# CH32V205CCT-R0.net
KiCad netlist of a schematic drawn in Altium Designer
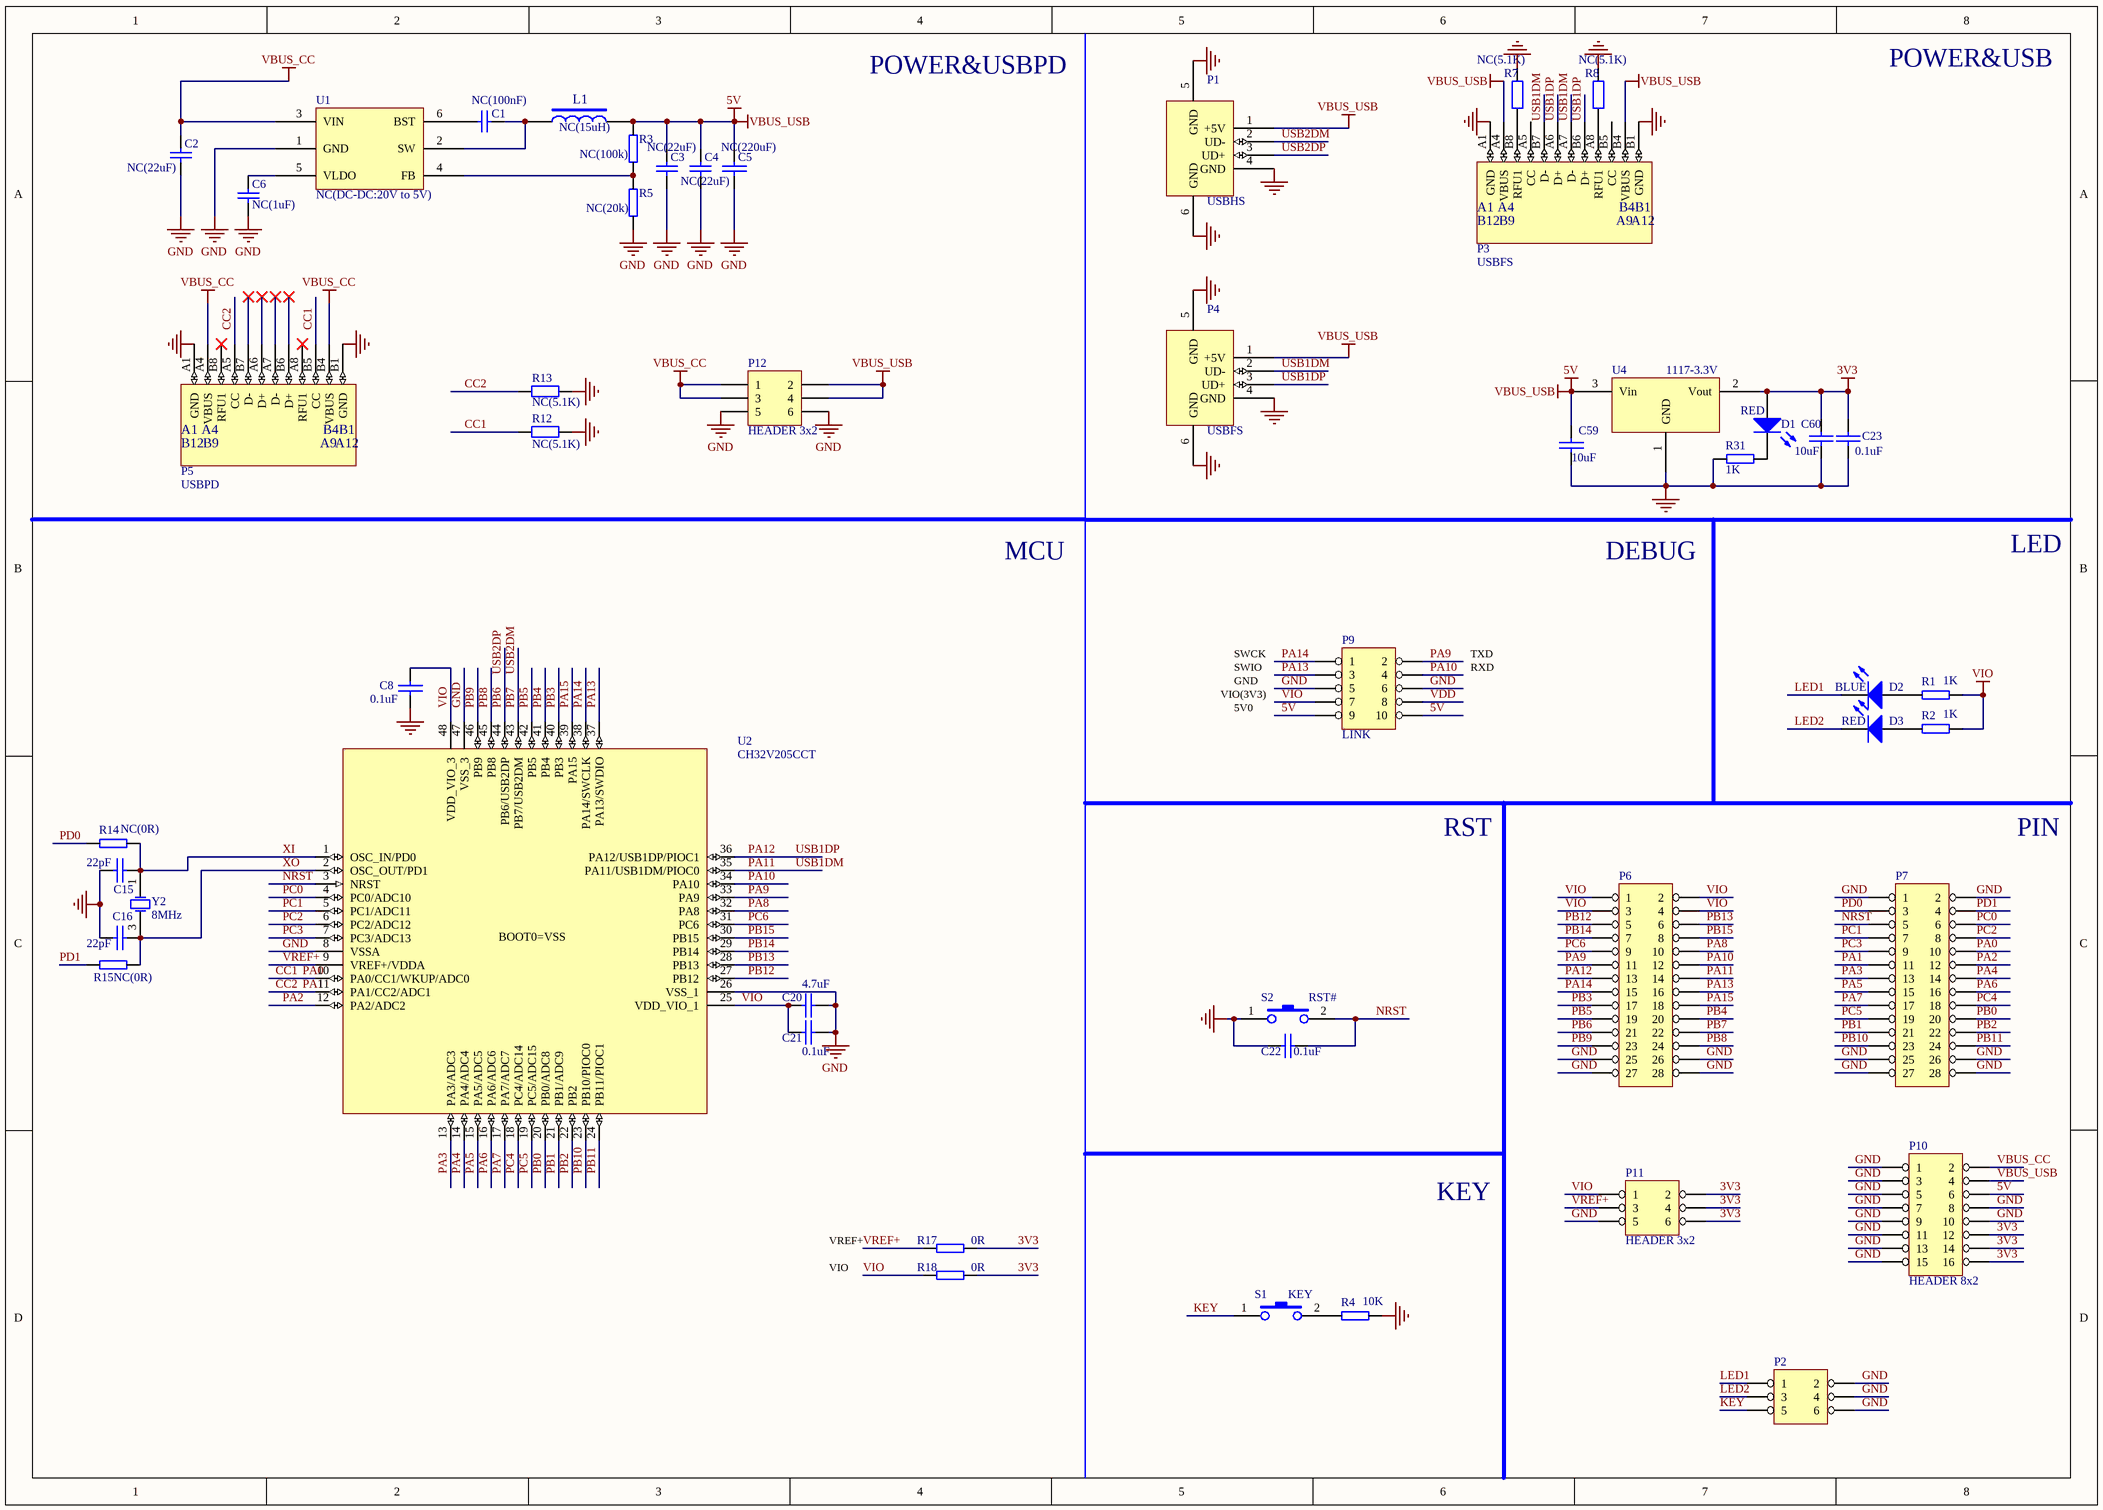
[diagram p0: CH32V205CCT-R0.SchDoc]

(export (version "E")
  (design (tool "Eeschema 10.0.6"))
  (components
    (comp (ref "C1")
      (value "NC(100nF)")
      (footprint "0402_C")
      (description "贴片电容")
      (libsource (lib "Miscellaneous Devices LC") (part "0603 100nF (104) 10% 50V"))
    )
    (comp (ref "C2")
      (value "NC(22uF)")
      (footprint "0805_C")
      (description "贴片电容")
      (libsource (lib "Miscellaneous Devices LC") (part "0603 100nF (104) 10% 50V"))
    )
    (comp (ref "C3")
      (value "NC(22uF)")
      (footprint "0805_C")
      (description "贴片电容")
      (libsource (lib "Miscellaneous Devices LC") (part "0603 100nF (104) 10% 50V"))
    )
    (comp (ref "C4")
      (value "NC(22uF)")
      (footprint "0805_C")
      (description "贴片电容")
      (libsource (lib "Miscellaneous Devices LC") (part "0603 100nF (104) 10% 50V"))
    )
    (comp (ref "C5")
      (value "NC(220uF)")
      (footprint "CD0.1")
      (description "Capacitor")
      (libsource (lib "") (part "CAP_1"))
    )
    (comp (ref "C6")
      (value "NC(1uF)")
      (footprint "0402_C")
      (description "贴片电容")
      (libsource (lib "Miscellaneous Devices LC") (part "0603 100nF (104) 10% 50V"))
    )
    (comp (ref "C8")
      (value "0.1uF")
      (footprint "0603_C")
      (description "Capacitor")
      (libsource (lib "*") (part "CAP"))
    )
    (comp (ref "C15")
      (value "22pF")
      (footprint "0603_C")
      (description "Capacitor")
      (libsource (lib "*") (part "CAP"))
    )
    (comp (ref "C16")
      (value "22pF")
      (footprint "0603_C")
      (description "Capacitor")
      (libsource (lib "*") (part "CAP"))
    )
    (comp (ref "C20")
      (value "4.7uF")
      (footprint "0603_C")
      (description "Capacitor")
      (libsource (lib "*") (part "CAP"))
    )
    (comp (ref "C21")
      (value "0.1uF")
      (footprint "0603_C")
      (description "Capacitor")
      (libsource (lib "*") (part "CAP"))
    )
    (comp (ref "C22")
      (value "0.1uF")
      (footprint "0603_C")
      (description "Capacitor")
      (libsource (lib "") (part "CAP_2"))
    )
    (comp (ref "C23")
      (value "0.1uF")
      (footprint "0402_C")
      (description "Capacitor")
      (libsource (lib "*") (part "CAP"))
    )
    (comp (ref "C59")
      (value "10uF")
      (footprint "0603_C")
      (description "Capacitor")
      (libsource (lib "*") (part "CAP"))
    )
    (comp (ref "C60")
      (value "10uF")
      (footprint "0603_C")
      (description "Capacitor")
      (libsource (lib "*") (part "CAP"))
    )
    (comp (ref "D1")
      (value "RED")
      (footprint "0603+")
      (description "Typical INFRARED GaAs LED")
      (fields (field (name "PUBLISHER") "Altium Limited"))
      (libsource (lib "*") (part "LED0"))
    )
    (comp (ref "D2")
      (value "BLUE")
      (footprint "0603+")
      (description "Typical INFRARED GaAs LED")
      (fields (field (name "PUBLISHER") "Altium Limited"))
      (libsource (lib "*") (part "LED0"))
    )
    (comp (ref "D3")
      (value "RED")
      (footprint "0603+")
      (description "Typical INFRARED GaAs LED")
      (fields (field (name "PUBLISHER") "Altium Limited"))
      (libsource (lib "*") (part "LED0"))
    )
    (comp (ref "L1")
      (value "NC(15uH)")
      (footprint "SMD_6x6mm")
      (libsource (lib "wch_sch_others") (part "INDUCTOR"))
    )
    (comp (ref "P1")
      (value "USBHS")
      (footprint "USBAF")
      (description "USB Port")
      (libsource (lib "*") (part "USB"))
    )
    (comp (ref "P2")
      (value "IO")
      (footprint "MYPCB:IDC6-2.54mm")
      (description "Header, 3-Pin, Dual row")
      (libsource (lib "wch_sch_others") (part "HEADER 3x2"))
    )
    (comp (ref "P3")
      (value "USBFS")
      (footprint "TYPE-C-Receptacle-2.0")
      (libsource (lib "*") (part "TYPE-C1"))
    )
    (comp (ref "P4")
      (value "USBFS")
      (footprint "USBAF")
      (description "USB Port")
      (libsource (lib "*") (part "USB"))
    )
    (comp (ref "P5")
      (value "USBPD")
      (footprint "TYPE-C-Receptacle-2.0")
      (libsource (lib "*") (part "TYPE-C1"))
    )
    (comp (ref "P6")
      (value "~")
      (footprint "MYPCB:IDC28-2.54MM")
      (description "Header, 14-Pin, Dual row")
      (libsource (lib "wch_sch_others") (part "HEADER 14x2"))
    )
    (comp (ref "P7")
      (value "~")
      (footprint "MYPCB:IDC28-2.54MM")
      (description "Header, 14-Pin, Dual row")
      (libsource (lib "wch_sch_others") (part "HEADER 14x2"))
    )
    (comp (ref "P9")
      (value "LINK")
      (footprint "MYPCB:IDC10-2.54mm")
      (description "Header, 5-Pin, Dual row")
      (libsource (lib "wch_sch_others") (part "HEADER 5x2"))
    )
    (comp (ref "P10")
      (value "HEADER 8x2")
      (footprint "MYPCB:IDC16-2.54mm")
      (description "Header, 8-Pin, Dual row")
      (libsource (lib "wch_sch_others") (part "HEADER 8x2"))
    )
    (comp (ref "P11")
      (value "HEADER 3x2")
      (footprint "MYPCB:IDC6-2.54mm")
      (description "Header, 3-Pin, Dual row")
      (libsource (lib "wch_sch_others") (part "HEADER 3x2"))
    )
    (comp (ref "P12")
      (value "HEADER 3x2")
      (footprint "MYPCB:IDC6-2.54mm")
      (description "Header, 3-Pin, Dual row")
      (libsource (lib "") (part "HEADER 3x2_1"))
    )
    (comp (ref "R1") (value "1K") (footprint "CHXXX:0603") (libsource (lib "wch_sch_others") (part "RES")))
    (comp (ref "R2") (value "1K") (footprint "CHXXX:0603") (libsource (lib "wch_sch_others") (part "RES")))
    (comp (ref "R3") (value "NC(100k)") (footprint "CHXXX:0603") (libsource (lib "") (part "RES_1")))
    (comp (ref "R4") (value "10K") (footprint "CHXXX:0603") (libsource (lib "wch_sch_others") (part "RES")))
    (comp (ref "R5") (value "NC(20k)") (footprint "CHXXX:0603") (libsource (lib "") (part "RES_1")))
    (comp (ref "R7")
      (value "NC(5.1K)")
      (footprint "0402")
      (description "Resistor")
      (libsource (lib "") (part "Res2_1"))
    )
    (comp (ref "R8")
      (value "NC(5.1K)")
      (footprint "0402")
      (description "Resistor")
      (libsource (lib "") (part "Res2_1"))
    )
    (comp (ref "R12")
      (value "NC(5.1K)")
      (footprint "0402")
      (description "Resistor")
      (libsource (lib "Miscellaneous Devices") (part "Res2"))
    )
    (comp (ref "R13")
      (value "NC(5.1K)")
      (footprint "0402")
      (description "Resistor")
      (libsource (lib "Miscellaneous Devices") (part "Res2"))
    )
    (comp (ref "R14")
      (value "NC(0R)")
      (footprint "CHXXX:0603")
      (libsource (lib "wch_sch_others") (part "RES"))
    )
    (comp (ref "R15")
      (value "NC(0R)")
      (footprint "CHXXX:0603")
      (libsource (lib "wch_sch_others") (part "RES"))
    )
    (comp (ref "R17") (value "0R") (footprint "CHXXX:0603") (libsource (lib "*") (part "R")))
    (comp (ref "R18") (value "0R") (footprint "CHXXX:0603") (libsource (lib "*") (part "R")))
    (comp (ref "R31") (value "1K") (footprint "0402") (libsource (lib "wch_sch_others") (part "RES")))
    (comp (ref "S1")
      (value "KEY")
      (footprint "SMD_6.1x3.65x2.5mm-KEY")
      (libsource (lib "wch_sch_others") (part "KEY1"))
    )
    (comp (ref "S2")
      (value "RST#")
      (footprint "SMD_6.1x3.65x2.5mm-KEY")
      (libsource (lib "wch_sch_others") (part "KEY1"))
    )
    (comp (ref "U1")
      (value "NC(DC-DC:20V to 5V)")
      (description "DCDC")
      (libsource (lib "wch_sch_others") (part "TPS54202"))
    )
    (comp (ref "U2")
      (value "CH32V205CCT")
      (footprint "LQFP48")
      (description "RISC-V MCU, 192MHz, USB_480M, USB FS, PD, PIOC, ADC, TKEY, 2*OPA, 2*CMP")
      (libsource (lib "CHXXX") (part "CH32V205CCT"))
    )
    (comp (ref "U4")
      (value "1117-3.3V")
      (footprint "SOT-223")
      (libsource (lib "wch_sch_others") (part "1117-3.3V"))
    )
    (comp (ref "Y2")
      (value "8MHz")
      (footprint "XT3225")
      (description "Crystal Oscillator")
      (fields (field (name "PUBLISHER") "Altium Limited"))
      (libsource (lib "*") (part "XTAL"))
    )
  )
  (nets
    (net (code "2") (name "/CC1") (class "Default")
      (node (ref "P5") (pin "B5") (pinfunction "CC_B5") (pintype "bidirectional"))
      (node (ref "P7") (pin "10") (pinfunction "10_10") (pintype "passive"))
      (node (ref "R12") (pin "1") (pinfunction "1_1") (pintype "passive"))
      (node (ref "U2") (pin "10") (pinfunction "PA0/CC1/WKUP/ADC0_10") (pintype "bidirectional"))
    )
    (net (code "3") (name "/CC2") (class "Default")
      (node (ref "P5") (pin "A5") (pinfunction "CC_A5") (pintype "bidirectional"))
      (node (ref "P7") (pin "11") (pinfunction "11_11") (pintype "passive"))
      (node (ref "R13") (pin "1") (pinfunction "1_1") (pintype "passive"))
      (node (ref "U2") (pin "11") (pinfunction "PA1/CC2/ADC1_11") (pintype "bidirectional"))
    )
    (net (code "4") (name "/KEY") (class "Default")
      (node (ref "P2") (pin "5") (pinfunction "5_5") (pintype "passive"))
      (node (ref "S1") (pin "1") (pinfunction "1_1") (pintype "passive"))
    )
    (net (code "5") (name "/LED1") (class "Default")
      (node (ref "D2") (pin "2") (pinfunction "K_2") (pintype "passive"))
      (node (ref "P2") (pin "1") (pinfunction "1_1") (pintype "passive"))
    )
    (net (code "6") (name "/LED2") (class "Default")
      (node (ref "D3") (pin "2") (pinfunction "K_2") (pintype "passive"))
      (node (ref "P2") (pin "3") (pinfunction "3_3") (pintype "passive"))
    )
    (net (code "7") (name "/NRST") (class "Default")
      (node (ref "C22") (pin "2") (pinfunction "2_2") (pintype "passive"))
      (node (ref "P7") (pin "5") (pinfunction "5_5") (pintype "passive"))
      (node (ref "S2") (pin "2") (pinfunction "2_2") (pintype "passive"))
      (node (ref "U2") (pin "3") (pinfunction "NRST_3") (pintype "input"))
    )
    (net (code "8") (name "/PA2") (class "Default")
      (node (ref "P7") (pin "12") (pinfunction "12_12") (pintype "passive"))
      (node (ref "U2") (pin "12") (pinfunction "PA2/ADC2_12") (pintype "bidirectional"))
    )
    (net (code "9") (name "/PA3") (class "Default")
      (node (ref "P7") (pin "13") (pinfunction "13_13") (pintype "passive"))
      (node (ref "U2") (pin "13") (pinfunction "PA3/ADC3_13") (pintype "bidirectional"))
    )
    (net (code "10") (name "/PA4") (class "Default")
      (node (ref "P7") (pin "14") (pinfunction "14_14") (pintype "passive"))
      (node (ref "U2") (pin "14") (pinfunction "PA4/ADC4_14") (pintype "bidirectional"))
    )
    (net (code "11") (name "/PA5") (class "Default")
      (node (ref "P7") (pin "15") (pinfunction "15_15") (pintype "passive"))
      (node (ref "U2") (pin "15") (pinfunction "PA5/ADC5_15") (pintype "bidirectional"))
    )
    (net (code "12") (name "/PA6") (class "Default")
      (node (ref "P7") (pin "16") (pinfunction "16_16") (pintype "passive"))
      (node (ref "U2") (pin "16") (pinfunction "PA6/ADC6_16") (pintype "bidirectional"))
    )
    (net (code "13") (name "/PA7") (class "Default")
      (node (ref "P7") (pin "17") (pinfunction "17_17") (pintype "passive"))
      (node (ref "U2") (pin "17") (pinfunction "PA7/ADC7_17") (pintype "bidirectional"))
    )
    (net (code "14") (name "/PA8") (class "Default")
      (node (ref "P6") (pin "10") (pinfunction "10_10") (pintype "passive"))
      (node (ref "U2") (pin "32") (pinfunction "PA8_32") (pintype "bidirectional"))
    )
    (net (code "15") (name "/PA9") (class "Default")
      (node (ref "P6") (pin "11") (pinfunction "11_11") (pintype "passive"))
      (node (ref "P9") (pin "2") (pinfunction "2_2") (pintype "passive"))
      (node (ref "U2") (pin "33") (pinfunction "PA9_33") (pintype "bidirectional"))
    )
    (net (code "16") (name "/PA10") (class "Default")
      (node (ref "P6") (pin "12") (pinfunction "12_12") (pintype "passive"))
      (node (ref "P9") (pin "4") (pinfunction "4_4") (pintype "passive"))
      (node (ref "U2") (pin "34") (pinfunction "PA10_34") (pintype "bidirectional"))
    )
    (net (code "17") (name "/PA11") (class "Default")
      (node (ref "P3") (pin "A7") (pinfunction "D-_A7") (pintype "bidirectional"))
      (node (ref "P3") (pin "B7") (pinfunction "D-_B7") (pintype "bidirectional"))
      (node (ref "P4") (pin "2") (pinfunction "UD-_2") (pintype "bidirectional"))
      (node (ref "P6") (pin "14") (pinfunction "14_14") (pintype "passive"))
      (node (ref "U2") (pin "35") (pinfunction "PA11/USB1DM/PIOC0_35") (pintype "bidirectional"))
    )
    (net (code "18") (name "/PA12") (class "Default")
      (node (ref "P3") (pin "A6") (pinfunction "D+_A6") (pintype "bidirectional"))
      (node (ref "P3") (pin "B6") (pinfunction "D+_B6") (pintype "bidirectional"))
      (node (ref "P4") (pin "3") (pinfunction "UD+_3") (pintype "bidirectional"))
      (node (ref "P6") (pin "13") (pinfunction "13_13") (pintype "passive"))
      (node (ref "U2") (pin "36") (pinfunction "PA12/USB1DP/PIOC1_36") (pintype "bidirectional"))
    )
    (net (code "19") (name "/PA13") (class "Default")
      (node (ref "P6") (pin "16") (pinfunction "16_16") (pintype "passive"))
      (node (ref "P9") (pin "3") (pinfunction "3_3") (pintype "passive"))
      (node (ref "U2") (pin "37") (pinfunction "PA13/SWDIO_37") (pintype "bidirectional"))
    )
    (net (code "20") (name "/PA14") (class "Default")
      (node (ref "P6") (pin "15") (pinfunction "15_15") (pintype "passive"))
      (node (ref "P9") (pin "1") (pinfunction "1_1") (pintype "passive"))
      (node (ref "U2") (pin "38") (pinfunction "PA14/SWCLK_38") (pintype "bidirectional"))
    )
    (net (code "21") (name "/PA15") (class "Default")
      (node (ref "P6") (pin "18") (pinfunction "18_18") (pintype "passive"))
      (node (ref "U2") (pin "39") (pinfunction "PA15_39") (pintype "bidirectional"))
    )
    (net (code "22") (name "/PB0") (class "Default")
      (node (ref "P7") (pin "20") (pinfunction "20_20") (pintype "passive"))
      (node (ref "U2") (pin "20") (pinfunction "PB0/ADC8_20") (pintype "bidirectional"))
    )
    (net (code "23") (name "/PB1") (class "Default")
      (node (ref "P7") (pin "21") (pinfunction "21_21") (pintype "passive"))
      (node (ref "U2") (pin "21") (pinfunction "PB1/ADC9_21") (pintype "bidirectional"))
    )
    (net (code "24") (name "/PB2") (class "Default")
      (node (ref "P7") (pin "22") (pinfunction "22_22") (pintype "passive"))
      (node (ref "U2") (pin "22") (pinfunction "PB2_22") (pintype "bidirectional"))
    )
    (net (code "25") (name "/PB3") (class "Default")
      (node (ref "P6") (pin "17") (pinfunction "17_17") (pintype "passive"))
      (node (ref "U2") (pin "40") (pinfunction "PB3_40") (pintype "bidirectional"))
    )
    (net (code "26") (name "/PB4") (class "Default")
      (node (ref "P6") (pin "20") (pinfunction "20_20") (pintype "passive"))
      (node (ref "U2") (pin "41") (pinfunction "PB4_41") (pintype "bidirectional"))
    )
    (net (code "27") (name "/PB5") (class "Default")
      (node (ref "P6") (pin "19") (pinfunction "19_19") (pintype "passive"))
      (node (ref "U2") (pin "42") (pinfunction "PB5_42") (pintype "bidirectional"))
    )
    (net (code "28") (name "/PB6") (class "Default")
      (node (ref "P1") (pin "3") (pinfunction "UD+_3") (pintype "bidirectional"))
      (node (ref "P6") (pin "21") (pinfunction "21_21") (pintype "passive"))
      (node (ref "U2") (pin "44") (pinfunction "PB6/USB2DP_44") (pintype "bidirectional"))
    )
    (net (code "29") (name "/PB7") (class "Default")
      (node (ref "P1") (pin "2") (pinfunction "UD-_2") (pintype "bidirectional"))
      (node (ref "P6") (pin "22") (pinfunction "22_22") (pintype "passive"))
      (node (ref "U2") (pin "43") (pinfunction "PB7/USB2DM_43") (pintype "bidirectional"))
    )
    (net (code "30") (name "/PB8") (class "Default")
      (node (ref "P6") (pin "24") (pinfunction "24_24") (pintype "passive"))
      (node (ref "U2") (pin "45") (pinfunction "PB8_45") (pintype "bidirectional"))
    )
    (net (code "31") (name "/PB9") (class "Default")
      (node (ref "P6") (pin "23") (pinfunction "23_23") (pintype "passive"))
      (node (ref "U2") (pin "46") (pinfunction "PB9_46") (pintype "bidirectional"))
    )
    (net (code "32") (name "/PB10") (class "Default")
      (node (ref "P7") (pin "23") (pinfunction "23_23") (pintype "passive"))
      (node (ref "U2") (pin "23") (pinfunction "PB10/PIOC0_23") (pintype "bidirectional"))
    )
    (net (code "33") (name "/PB11") (class "Default")
      (node (ref "P7") (pin "24") (pinfunction "24_24") (pintype "passive"))
      (node (ref "U2") (pin "24") (pinfunction "PB11/PIOC1_24") (pintype "bidirectional"))
    )
    (net (code "34") (name "/PB12") (class "Default")
      (node (ref "P6") (pin "5") (pinfunction "5_5") (pintype "passive"))
      (node (ref "U2") (pin "27") (pinfunction "PB12_27") (pintype "bidirectional"))
    )
    (net (code "35") (name "/PB13") (class "Default")
      (node (ref "P6") (pin "6") (pinfunction "6_6") (pintype "passive"))
      (node (ref "U2") (pin "28") (pinfunction "PB13_28") (pintype "bidirectional"))
    )
    (net (code "36") (name "/PB14") (class "Default")
      (node (ref "P6") (pin "7") (pinfunction "7_7") (pintype "passive"))
      (node (ref "U2") (pin "29") (pinfunction "PB14_29") (pintype "bidirectional"))
    )
    (net (code "37") (name "/PB15") (class "Default")
      (node (ref "P6") (pin "8") (pinfunction "8_8") (pintype "passive"))
      (node (ref "U2") (pin "30") (pinfunction "PB15_30") (pintype "bidirectional"))
    )
    (net (code "38") (name "/PC0") (class "Default")
      (node (ref "P7") (pin "6") (pinfunction "6_6") (pintype "passive"))
      (node (ref "U2") (pin "4") (pinfunction "PC0/ADC10_4") (pintype "bidirectional"))
    )
    (net (code "39") (name "/PC1") (class "Default")
      (node (ref "P7") (pin "7") (pinfunction "7_7") (pintype "passive"))
      (node (ref "U2") (pin "5") (pinfunction "PC1/ADC11_5") (pintype "bidirectional"))
    )
    (net (code "40") (name "/PC2") (class "Default")
      (node (ref "P7") (pin "8") (pinfunction "8_8") (pintype "passive"))
      (node (ref "U2") (pin "6") (pinfunction "PC2/ADC12_6") (pintype "bidirectional"))
    )
    (net (code "41") (name "/PC3") (class "Default")
      (node (ref "P7") (pin "9") (pinfunction "9_9") (pintype "passive"))
      (node (ref "U2") (pin "7") (pinfunction "PC3/ADC13_7") (pintype "bidirectional"))
    )
    (net (code "42") (name "/PC4") (class "Default")
      (node (ref "P7") (pin "18") (pinfunction "18_18") (pintype "passive"))
      (node (ref "U2") (pin "18") (pinfunction "PC4/ADC14_18") (pintype "bidirectional"))
    )
    (net (code "43") (name "/PC5") (class "Default")
      (node (ref "P7") (pin "19") (pinfunction "19_19") (pintype "passive"))
      (node (ref "U2") (pin "19") (pinfunction "PC5/ADC15_19") (pintype "bidirectional"))
    )
    (net (code "44") (name "/PC6") (class "Default")
      (node (ref "P6") (pin "9") (pinfunction "9_9") (pintype "passive"))
      (node (ref "U2") (pin "31") (pinfunction "PC6_31") (pintype "bidirectional"))
    )
    (net (code "45") (name "/PD0") (class "Default")
      (node (ref "P7") (pin "3") (pinfunction "3_3") (pintype "passive"))
      (node (ref "R14") (pin "1") (pintype "passive"))
    )
    (net (code "46") (name "/PD1") (class "Default")
      (node (ref "P7") (pin "4") (pinfunction "4_4") (pintype "passive"))
      (node (ref "R15") (pin "1") (pintype "passive"))
    )
    (net (code "47") (name "/VDD") (class "Default")
      (node (ref "P9") (pin "8") (pinfunction "8_8") (pintype "passive"))
    )
    (net (code "48") (name "/VREF+") (class "Default")
      (node (ref "P11") (pin "3") (pinfunction "3_3") (pintype "passive"))
      (node (ref "R17") (pin "2") (pinfunction "2_2") (pintype "passive"))
      (node (ref "U2") (pin "9") (pinfunction "VREF+/VDDA_9") (pintype "power_in"))
    )
    (net (code "49") (name "/XI") (class "Default")
      (node (ref "C15") (pin "2") (pinfunction "2_2") (pintype "passive"))
      (node (ref "R14") (pin "2") (pintype "passive"))
      (node (ref "U2") (pin "1") (pinfunction "OSC_IN/PD0_1") (pintype "bidirectional"))
      (node (ref "Y2") (pin "1") (pinfunction "OSC1_1") (pintype "passive"))
    )
    (net (code "50") (name "/XO") (class "Default")
      (node (ref "C16") (pin "2") (pinfunction "2_2") (pintype "passive"))
      (node (ref "R15") (pin "2") (pintype "passive"))
      (node (ref "U2") (pin "2") (pinfunction "OSC_OUT/PD1_2") (pintype "bidirectional"))
      (node (ref "Y2") (pin "3") (pinfunction "OSC2_3") (pintype "passive"))
    )
    (net (code "51") (name "3V3") (class "Default")
      (node (ref "C23") (pin "1") (pinfunction "1_1") (pintype "passive"))
      (node (ref "C60") (pin "1") (pinfunction "1_1") (pintype "passive"))
      (node (ref "D1") (pin "1") (pinfunction "A_1") (pintype "passive"))
      (node (ref "P10") (pin "12") (pinfunction "12_12") (pintype "passive"))
      (node (ref "P10") (pin "14") (pinfunction "14_14") (pintype "passive"))
      (node (ref "P10") (pin "16") (pinfunction "16_16") (pintype "passive"))
      (node (ref "P11") (pin "2") (pinfunction "2_2") (pintype "passive"))
      (node (ref "P11") (pin "4") (pinfunction "4_4") (pintype "passive"))
      (node (ref "P11") (pin "6") (pinfunction "6_6") (pintype "passive"))
      (node (ref "R17") (pin "1") (pinfunction "1_1") (pintype "passive"))
      (node (ref "R18") (pin "1") (pinfunction "1_1") (pintype "passive"))
      (node (ref "U4") (pin "2") (pinfunction "Vout_2") (pintype "passive"))
    )
    (net (code "52") (name "5V") (class "Default")
      (node (ref "C3") (pin "2") (pinfunction "2_2") (pintype "passive"))
      (node (ref "C4") (pin "2") (pinfunction "2_2") (pintype "passive"))
      (node (ref "C5") (pin "1") (pinfunction "1_1") (pintype "passive"))
      (node (ref "C59") (pin "1") (pinfunction "1_1") (pintype "passive"))
      (node (ref "L1") (pin "2") (pinfunction "2_2") (pintype "passive"))
      (node (ref "P1") (pin "1") (pinfunction "+5V_1") (pintype "power_in"))
      (node (ref "P10") (pin "4") (pinfunction "4_4") (pintype "passive"))
      (node (ref "P10") (pin "6") (pinfunction "6_6") (pintype "passive"))
      (node (ref "P12") (pin "2") (pinfunction "2_2") (pintype "passive"))
      (node (ref "P12") (pin "4") (pinfunction "4_4") (pintype "passive"))
      (node (ref "P3") (pin "A4") (pinfunction "VBUS_A4") (pintype "bidirectional"))
      (node (ref "P3") (pin "B4") (pinfunction "VBUS_B4") (pintype "bidirectional"))
      (node (ref "P4") (pin "1") (pinfunction "+5V_1") (pintype "power_in"))
      (node (ref "P9") (pin "10") (pinfunction "10_10") (pintype "passive"))
      (node (ref "P9") (pin "9") (pinfunction "9_9") (pintype "passive"))
      (node (ref "R3") (pin "2") (pintype "passive"))
      (node (ref "U4") (pin "3") (pinfunction "Vin_3") (pintype "passive"))
    )
    (net (code "53") (name "GND") (class "Default")
      (node (ref "C15") (pin "1") (pinfunction "1_1") (pintype "passive"))
      (node (ref "C16") (pin "1") (pinfunction "1_1") (pintype "passive"))
      (node (ref "C2") (pin "1") (pinfunction "1_1") (pintype "passive"))
      (node (ref "C20") (pin "1") (pinfunction "1_1") (pintype "passive"))
      (node (ref "C21") (pin "1") (pinfunction "1_1") (pintype "passive"))
      (node (ref "C22") (pin "1") (pinfunction "1_1") (pintype "passive"))
      (node (ref "C23") (pin "2") (pinfunction "2_2") (pintype "passive"))
      (node (ref "C3") (pin "1") (pinfunction "1_1") (pintype "passive"))
      (node (ref "C4") (pin "1") (pinfunction "1_1") (pintype "passive"))
      (node (ref "C5") (pin "2") (pinfunction "2_2") (pintype "passive"))
      (node (ref "C59") (pin "2") (pinfunction "2_2") (pintype "passive"))
      (node (ref "C6") (pin "1") (pinfunction "1_1") (pintype "passive"))
      (node (ref "C60") (pin "2") (pinfunction "2_2") (pintype "passive"))
      (node (ref "C8") (pin "1") (pinfunction "1_1") (pintype "passive"))
      (node (ref "P1") (pin "4") (pinfunction "GND_4") (pintype "power_in"))
      (node (ref "P1") (pin "5") (pinfunction "GND_5") (pintype "power_in"))
      (node (ref "P1") (pin "6") (pinfunction "GND_6") (pintype "power_in"))
      (node (ref "P10") (pin "1") (pinfunction "1_1") (pintype "passive"))
      (node (ref "P10") (pin "10") (pinfunction "10_10") (pintype "passive"))
      (node (ref "P10") (pin "11") (pinfunction "11_11") (pintype "passive"))
      (node (ref "P10") (pin "13") (pinfunction "13_13") (pintype "passive"))
      (node (ref "P10") (pin "15") (pinfunction "15_15") (pintype "passive"))
      (node (ref "P10") (pin "3") (pinfunction "3_3") (pintype "passive"))
      (node (ref "P10") (pin "5") (pinfunction "5_5") (pintype "passive"))
      (node (ref "P10") (pin "7") (pinfunction "7_7") (pintype "passive"))
      (node (ref "P10") (pin "8") (pinfunction "8_8") (pintype "passive"))
      (node (ref "P10") (pin "9") (pinfunction "9_9") (pintype "passive"))
      (node (ref "P11") (pin "5") (pinfunction "5_5") (pintype "passive"))
      (node (ref "P12") (pin "5") (pinfunction "5_5") (pintype "passive"))
      (node (ref "P12") (pin "6") (pinfunction "6_6") (pintype "passive"))
      (node (ref "P2") (pin "2") (pinfunction "2_2") (pintype "passive"))
      (node (ref "P2") (pin "4") (pinfunction "4_4") (pintype "passive"))
      (node (ref "P2") (pin "6") (pinfunction "6_6") (pintype "passive"))
      (node (ref "P3") (pin "A1") (pinfunction "GND_A1") (pintype "bidirectional"))
      (node (ref "P3") (pin "B1") (pinfunction "GND_B1") (pintype "bidirectional"))
      (node (ref "P4") (pin "4") (pinfunction "GND_4") (pintype "power_in"))
      (node (ref "P4") (pin "5") (pinfunction "GND_5") (pintype "power_in"))
      (node (ref "P4") (pin "6") (pinfunction "GND_6") (pintype "power_in"))
      (node (ref "P5") (pin "A1") (pinfunction "GND_A1") (pintype "bidirectional"))
      (node (ref "P5") (pin "B1") (pinfunction "GND_B1") (pintype "bidirectional"))
      (node (ref "P6") (pin "25") (pinfunction "25_25") (pintype "passive"))
      (node (ref "P6") (pin "26") (pinfunction "26_26") (pintype "passive"))
      (node (ref "P6") (pin "27") (pinfunction "27_27") (pintype "passive"))
      (node (ref "P6") (pin "28") (pinfunction "28_28") (pintype "passive"))
      (node (ref "P7") (pin "1") (pinfunction "1_1") (pintype "passive"))
      (node (ref "P7") (pin "2") (pinfunction "2_2") (pintype "passive"))
      (node (ref "P7") (pin "25") (pinfunction "25_25") (pintype "passive"))
      (node (ref "P7") (pin "26") (pinfunction "26_26") (pintype "passive"))
      (node (ref "P7") (pin "27") (pinfunction "27_27") (pintype "passive"))
      (node (ref "P7") (pin "28") (pinfunction "28_28") (pintype "passive"))
      (node (ref "P9") (pin "5") (pinfunction "5_5") (pintype "passive"))
      (node (ref "P9") (pin "6") (pinfunction "6_6") (pintype "passive"))
      (node (ref "R12") (pin "2") (pinfunction "2_2") (pintype "passive"))
      (node (ref "R13") (pin "2") (pinfunction "2_2") (pintype "passive"))
      (node (ref "R31") (pin "1") (pintype "passive"))
      (node (ref "R4") (pin "1") (pintype "passive"))
      (node (ref "R5") (pin "1") (pintype "passive"))
      (node (ref "R7") (pin "2") (pinfunction "2_2") (pintype "passive"))
      (node (ref "R8") (pin "2") (pinfunction "2_2") (pintype "passive"))
      (node (ref "S2") (pin "1") (pinfunction "1_1") (pintype "passive"))
      (node (ref "U1") (pin "1") (pinfunction "GND_1") (pintype "passive"))
      (node (ref "U2") (pin "26") (pinfunction "VSS_1_26") (pintype "power_in"))
      (node (ref "U2") (pin "47") (pinfunction "VSS_3_47") (pintype "power_in"))
      (node (ref "U2") (pin "8") (pinfunction "VSSA_8") (pintype "power_in"))
      (node (ref "U4") (pin "1") (pinfunction "GND_1") (pintype "passive"))
    )
    (net (code "54") (name "Net-(D1-K)") (class "Default")
      (node (ref "D1") (pin "2") (pinfunction "K_2") (pintype "passive"))
      (node (ref "R31") (pin "2") (pintype "passive"))
    )
    (net (code "55") (name "Net-(D2-A)") (class "Default")
      (node (ref "D2") (pin "1") (pinfunction "A_1") (pintype "passive"))
      (node (ref "R1") (pin "2") (pintype "passive"))
    )
    (net (code "56") (name "Net-(D3-A)") (class "Default")
      (node (ref "D3") (pin "1") (pinfunction "A_1") (pintype "passive"))
      (node (ref "R2") (pin "2") (pintype "passive"))
    )
    (net (code "57") (name "Net-(P3-RFU1-PadA8)") (class "Default")
      (node (ref "P3") (pin "A8") (pinfunction "RFU1_A8") (pintype "bidirectional"))
      (node (ref "R8") (pin "1") (pinfunction "1_1") (pintype "passive"))
    )
    (net (code "58") (name "Net-(P3-RFU1-PadB8)") (class "Default")
      (node (ref "P3") (pin "B8") (pinfunction "RFU1_B8") (pintype "bidirectional"))
      (node (ref "R7") (pin "1") (pinfunction "1_1") (pintype "passive"))
    )
    (net (code "59") (name "Net-(R4-Pad2)") (class "Default")
      (node (ref "R4") (pin "2") (pintype "passive"))
      (node (ref "S1") (pin "2") (pinfunction "2_2") (pintype "passive"))
    )
    (net (code "60") (name "Net-(U1-BST)") (class "Default")
      (node (ref "C1") (pin "2") (pinfunction "2_2") (pintype "passive"))
      (node (ref "U1") (pin "6") (pinfunction "BST_6") (pintype "passive"))
    )
    (net (code "61") (name "Net-(U1-FB)") (class "Default")
      (node (ref "R3") (pin "1") (pintype "passive"))
      (node (ref "R5") (pin "2") (pintype "passive"))
      (node (ref "U1") (pin "4") (pinfunction "FB_4") (pintype "passive"))
    )
    (net (code "62") (name "Net-(U1-SW)") (class "Default")
      (node (ref "C1") (pin "1") (pinfunction "1_1") (pintype "passive"))
      (node (ref "L1") (pin "1") (pinfunction "1_1") (pintype "passive"))
      (node (ref "U1") (pin "2") (pinfunction "SW_2") (pintype "passive"))
    )
    (net (code "63") (name "Net-(U1-VLDO)") (class "Default")
      (node (ref "C6") (pin "2") (pinfunction "2_2") (pintype "passive"))
      (node (ref "U1") (pin "5") (pinfunction "VLDO_5") (pintype "passive"))
    )
    (net (code "64") (name "VBUS_CC") (class "Default")
      (node (ref "C2") (pin "2") (pinfunction "2_2") (pintype "passive"))
      (node (ref "P10") (pin "2") (pinfunction "2_2") (pintype "passive"))
      (node (ref "P12") (pin "1") (pinfunction "1_1") (pintype "passive"))
      (node (ref "P12") (pin "3") (pinfunction "3_3") (pintype "passive"))
      (node (ref "P5") (pin "A4") (pinfunction "VBUS_A4") (pintype "bidirectional"))
      (node (ref "P5") (pin "B4") (pinfunction "VBUS_B4") (pintype "bidirectional"))
      (node (ref "U1") (pin "3") (pinfunction "VIN_3") (pintype "passive"))
    )
    (net (code "65") (name "VIO") (class "Default")
      (node (ref "C20") (pin "2") (pinfunction "2_2") (pintype "passive"))
      (node (ref "C21") (pin "2") (pinfunction "2_2") (pintype "passive"))
      (node (ref "C8") (pin "2") (pinfunction "2_2") (pintype "passive"))
      (node (ref "P11") (pin "1") (pinfunction "1_1") (pintype "passive"))
      (node (ref "P6") (pin "1") (pinfunction "1_1") (pintype "passive"))
      (node (ref "P6") (pin "2") (pinfunction "2_2") (pintype "passive"))
      (node (ref "P6") (pin "3") (pinfunction "3_3") (pintype "passive"))
      (node (ref "P6") (pin "4") (pinfunction "4_4") (pintype "passive"))
      (node (ref "P9") (pin "7") (pinfunction "7_7") (pintype "passive"))
      (node (ref "R1") (pin "1") (pintype "passive"))
      (node (ref "R18") (pin "2") (pinfunction "2_2") (pintype "passive"))
      (node (ref "R2") (pin "1") (pintype "passive"))
      (node (ref "U2") (pin "25") (pinfunction "VDD_VIO_1_25") (pintype "power_in"))
      (node (ref "U2") (pin "48") (pinfunction "VDD_VIO_3_48") (pintype "power_in"))
    )
    (net (code "66") (name "unconnected-(P3-CC-PadA5)") (class "Default")
      (node (ref "P3") (pin "A5") (pinfunction "CC_A5") (pintype "bidirectional"))
    )
    (net (code "67") (name "unconnected-(P3-CC-PadB5)") (class "Default")
      (node (ref "P3") (pin "B5") (pinfunction "CC_B5") (pintype "bidirectional"))
    )
    (net (code "68") (name "unconnected-(P5-D+-PadA6)") (class "Default")
      (node (ref "P5") (pin "A6") (pinfunction "D+_A6") (pintype "bidirectional+no_connect"))
    )
    (net (code "69") (name "unconnected-(P5-D+-PadB6)") (class "Default")
      (node (ref "P5") (pin "B6") (pinfunction "D+_B6") (pintype "bidirectional+no_connect"))
    )
    (net (code "70") (name "unconnected-(P5-D--PadA7)") (class "Default")
      (node (ref "P5") (pin "A7") (pinfunction "D-_A7") (pintype "bidirectional+no_connect"))
    )
    (net (code "71") (name "unconnected-(P5-D--PadB7)") (class "Default")
      (node (ref "P5") (pin "B7") (pinfunction "D-_B7") (pintype "bidirectional+no_connect"))
    )
    (net (code "72") (name "unconnected-(P5-RFU1-PadA8)") (class "Default")
      (node (ref "P5") (pin "A8") (pinfunction "RFU1_A8") (pintype "bidirectional+no_connect"))
    )
    (net (code "73") (name "unconnected-(P5-RFU1-PadB8)") (class "Default")
      (node (ref "P5") (pin "B8") (pinfunction "RFU1_B8") (pintype "bidirectional+no_connect"))
    )
  )
)
